# Adafruit_2_13in_eInk_Bonnet.net
KiCad netlist of a schematic drawn in EAGLE
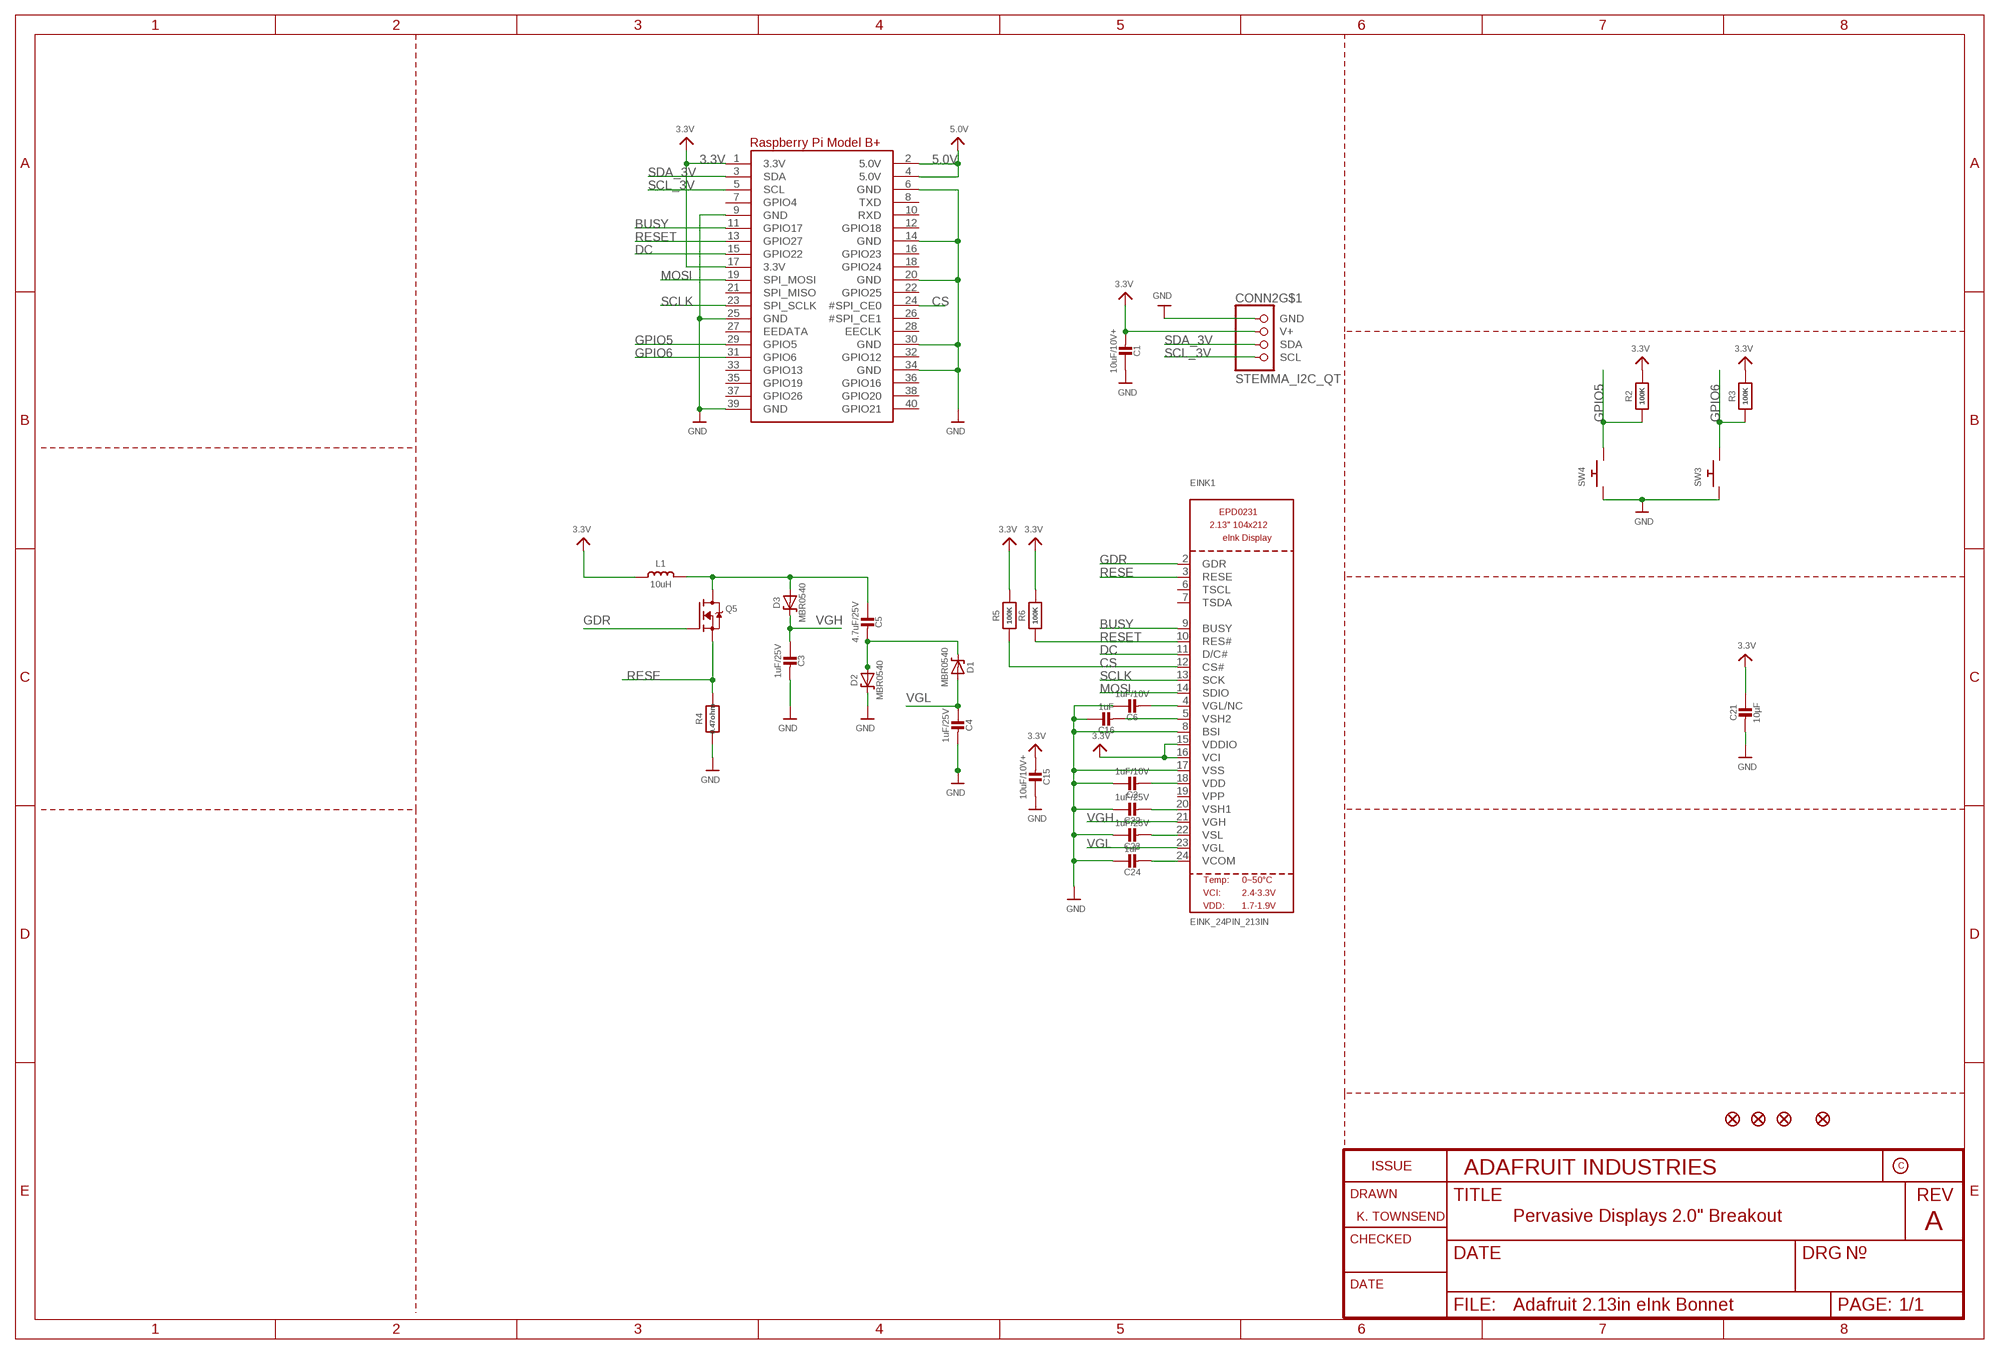
[diagram p0: schematic, sheet 1]

(export (version "E")
  (design (tool "Eeschema 10.0.6"))
  (components
    (comp (ref "C1")
      (value "10uF/10V+")
      (footprint "eagle-import:0805-NO")
      (libsource (lib "eagle-import") (part "CAP_CERAMIC0805-NOOUTLINE"))
    )
    (comp (ref "C2")
      (value "1uF/10V")
      (footprint "eagle-import:0805-NO")
      (libsource (lib "eagle-import") (part "CAP_CERAMIC0805-NOOUTLINE"))
    )
    (comp (ref "C3")
      (value "1uF/25V")
      (footprint "eagle-import:0805-NO")
      (libsource (lib "eagle-import") (part "CAP_CERAMIC0805-NOOUTLINE"))
    )
    (comp (ref "C4")
      (value "1uF/25V")
      (footprint "eagle-import:0805-NO")
      (libsource (lib "eagle-import") (part "CAP_CERAMIC0805-NOOUTLINE"))
    )
    (comp (ref "C5")
      (value "4.7uF/25V")
      (footprint "eagle-import:0805-NO")
      (libsource (lib "eagle-import") (part "CAP_CERAMIC0805-NOOUTLINE"))
    )
    (comp (ref "C6")
      (value "1uF/10V")
      (footprint "eagle-import:0805-NO")
      (libsource (lib "eagle-import") (part "CAP_CERAMIC0805-NOOUTLINE"))
    )
    (comp (ref "C15")
      (value "10uF/10V+")
      (footprint "eagle-import:0805-NO")
      (libsource (lib "eagle-import") (part "CAP_CERAMIC0805-NOOUTLINE"))
    )
    (comp (ref "C16")
      (value "1uF")
      (footprint "eagle-import:0805-NO")
      (libsource (lib "eagle-import") (part "CAP_CERAMIC0805-NOOUTLINE"))
    )
    (comp (ref "C21")
      (value "10µF")
      (footprint "eagle-import:0805-NO")
      (libsource (lib "eagle-import") (part "CAP_CERAMIC0805-NOOUTLINE"))
    )
    (comp (ref "C22")
      (value "1uF/25V")
      (footprint "eagle-import:0805-NO")
      (libsource (lib "eagle-import") (part "CAP_CERAMIC0805-NOOUTLINE"))
    )
    (comp (ref "C23")
      (value "1uF/25V")
      (footprint "eagle-import:0805-NO")
      (libsource (lib "eagle-import") (part "CAP_CERAMIC0805-NOOUTLINE"))
    )
    (comp (ref "C24")
      (value "1uF")
      (footprint "eagle-import:0805-NO")
      (libsource (lib "eagle-import") (part "CAP_CERAMIC0805-NOOUTLINE"))
    )
    (comp (ref "CONN2")
      (value "STEMMA_I2C_QT")
      (footprint "eagle-import:JST_SH4")
      (libsource (lib "eagle-import") (part "STEMMA_I2C_QT"))
    )
    (comp (ref "D1")
      (value "MBR0540")
      (footprint "eagle-import:SOD-123")
      (libsource (lib "eagle-import") (part "DIODE-SCHOTTKYSOD-123"))
    )
    (comp (ref "D2")
      (value "MBR0540")
      (footprint "eagle-import:SOD-123")
      (libsource (lib "eagle-import") (part "DIODE-SCHOTTKYSOD-123"))
    )
    (comp (ref "D3")
      (value "MBR0540")
      (footprint "eagle-import:SOD-123")
      (libsource (lib "eagle-import") (part "DIODE-SCHOTTKYSOD-123"))
    )
    (comp (ref "EINK1")
      (value "EINK_24PIN_213IN")
      (footprint "eagle-import:EINK_213IN_104X212")
      (libsource (lib "eagle-import") (part "EINK_24PIN_213IN"))
    )
    (comp (ref "FID1")
      (value "FIDUCIAL_1MM")
      (footprint "eagle-import:FIDUCIAL_1MM")
      (libsource (lib "eagle-import") (part "FIDUCIAL_1MM"))
    )
    (comp (ref "FID2")
      (value "FIDUCIAL_1MM")
      (footprint "eagle-import:FIDUCIAL_1MM")
      (libsource (lib "eagle-import") (part "FIDUCIAL_1MM"))
    )
    (comp (ref "FID3")
      (value "FIDUCIAL_1MM")
      (footprint "eagle-import:FIDUCIAL_1MM")
      (libsource (lib "eagle-import") (part "FIDUCIAL_1MM"))
    )
    (comp (ref "FID4")
      (value "FIDUCIAL_1MM")
      (footprint "eagle-import:FIDUCIAL_1MM")
      (libsource (lib "eagle-import") (part "FIDUCIAL_1MM"))
    )
    (comp (ref "L1")
      (value "10uH")
      (footprint "eagle-import:INDUCTOR_4X4MM_NR401")
      (libsource (lib "eagle-import") (part "INDUCTORNR401"))
    )
    (comp (ref "Q5")
      (value "IRLML0100")
      (footprint "eagle-import:SOT23-3")
      (libsource (lib "eagle-import") (part "IRLML2060TRPBF"))
    )
    (comp (ref "R2")
      (value "100K")
      (footprint "eagle-import:0603-NO")
      (libsource (lib "eagle-import") (part "RESISTOR_0603_NOOUT"))
    )
    (comp (ref "R3")
      (value "100K")
      (footprint "eagle-import:0603-NO")
      (libsource (lib "eagle-import") (part "RESISTOR_0603_NOOUT"))
    )
    (comp (ref "R4")
      (value "0.47ohm")
      (footprint "eagle-import:0805_10MGAP")
      (libsource (lib "eagle-import") (part "RESISTOR0805_10MGAP"))
    )
    (comp (ref "R5")
      (value "100K")
      (footprint "eagle-import:0603-NO")
      (libsource (lib "eagle-import") (part "RESISTOR_0603_NOOUT"))
    )
    (comp (ref "R6")
      (value "100K")
      (footprint "eagle-import:0603-NO")
      (libsource (lib "eagle-import") (part "RESISTOR_0603_NOOUT"))
    )
    (comp (ref "RPI2")
      (value "RASPBERRYPI_BPLUS_SMT_NODIM")
      (footprint "eagle-import:PI_BONNET_SMT_NODIM")
      (libsource (lib "eagle-import") (part "RASPBERRYPI_BPLUS_SMT_NODIM"))
    )
    (comp (ref "SW3")
      (value "SWITCH_PUSHBUTTON_3.5X6MM")
      (footprint "eagle-import:TACTILE_3X6MM")
      (libsource (lib "eagle-import") (part "SWITCH_PUSHBUTTON_3.5X6MM"))
    )
    (comp (ref "SW4")
      (value "SWITCH_PUSHBUTTON_3.5X6MM")
      (footprint "eagle-import:TACTILE_3X6MM")
      (libsource (lib "eagle-import") (part "SWITCH_PUSHBUTTON_3.5X6MM"))
    )
  )
  (nets
    (net (code "1") (name "/BUSY") (class "Default")
      (node (ref "EINK1") (pin "9") (pinfunction "BUSY_9") (pintype "output"))
      (node (ref "RPI2") (pin "11") (pinfunction "GPIO17_11") (pintype "bidirectional"))
    )
    (net (code "2") (name "/CS") (class "Default")
      (node (ref "EINK1") (pin "12") (pinfunction "CS#_12") (pintype "input"))
      (node (ref "R5") (pin "1") (pinfunction "1_1") (pintype "passive"))
      (node (ref "RPI2") (pin "24") (pinfunction "#SPI_CE0_24") (pintype "bidirectional"))
    )
    (net (code "3") (name "/DC") (class "Default")
      (node (ref "EINK1") (pin "11") (pinfunction "D/C#_11") (pintype "input"))
      (node (ref "RPI2") (pin "15") (pinfunction "GPIO22_15") (pintype "bidirectional"))
    )
    (net (code "4") (name "/GDR") (class "Default")
      (node (ref "EINK1") (pin "2") (pinfunction "GDR_2") (pintype "output"))
      (node (ref "Q5") (pin "1") (pinfunction "G_1") (pintype "bidirectional"))
    )
    (net (code "5") (name "/GPIO5") (class "Default")
      (node (ref "R2") (pin "1") (pinfunction "1_1") (pintype "passive"))
      (node (ref "RPI2") (pin "29") (pinfunction "GPIO5_29") (pintype "bidirectional"))
      (node (ref "SW4") (pin "P$2") (pinfunction "P$2_P$2") (pintype "passive"))
    )
    (net (code "6") (name "/GPIO6") (class "Default")
      (node (ref "R3") (pin "1") (pinfunction "1_1") (pintype "passive"))
      (node (ref "RPI2") (pin "31") (pinfunction "GPIO6_31") (pintype "bidirectional"))
      (node (ref "SW3") (pin "P$2") (pinfunction "P$2_P$2") (pintype "passive"))
    )
    (net (code "7") (name "/MOSI") (class "Default")
      (node (ref "EINK1") (pin "14") (pinfunction "SDIO_14") (pintype "bidirectional"))
      (node (ref "RPI2") (pin "19") (pinfunction "SPI_MOSI_19") (pintype "bidirectional"))
    )
    (net (code "8") (name "/RESE") (class "Default")
      (node (ref "EINK1") (pin "3") (pinfunction "RESE_3") (pintype "input"))
      (node (ref "Q5") (pin "2") (pinfunction "S_2") (pintype "bidirectional"))
      (node (ref "R4") (pin "1") (pinfunction "1_1") (pintype "passive"))
    )
    (net (code "9") (name "/RESET") (class "Default")
      (node (ref "EINK1") (pin "10") (pinfunction "RES#_10") (pintype "input"))
      (node (ref "R6") (pin "1") (pinfunction "1_1") (pintype "passive"))
      (node (ref "RPI2") (pin "13") (pinfunction "GPIO27_13") (pintype "bidirectional"))
    )
    (net (code "10") (name "/SCLK") (class "Default")
      (node (ref "EINK1") (pin "13") (pinfunction "SCK_13") (pintype "bidirectional"))
      (node (ref "RPI2") (pin "23") (pinfunction "SPI_SCLK_23") (pintype "bidirectional"))
    )
    (net (code "11") (name "/SCL_3V") (class "Default")
      (node (ref "CONN2") (pin "4") (pinfunction "SCL_4") (pintype "passive"))
      (node (ref "RPI2") (pin "5") (pinfunction "SCL_5") (pintype "bidirectional"))
    )
    (net (code "12") (name "/SDA_3V") (class "Default")
      (node (ref "CONN2") (pin "3") (pinfunction "SDA_3") (pintype "passive"))
      (node (ref "RPI2") (pin "3") (pinfunction "SDA_3") (pintype "bidirectional"))
    )
    (net (code "13") (name "/VGH") (class "Default")
      (node (ref "C3") (pin "1") (pinfunction "1_1") (pintype "passive"))
      (node (ref "D3") (pin "C") (pinfunction "C_C") (pintype "passive"))
      (node (ref "EINK1") (pin "21") (pinfunction "VGH_21") (pintype "passive"))
    )
    (net (code "14") (name "/VGL") (class "Default")
      (node (ref "C4") (pin "1") (pinfunction "1_1") (pintype "passive"))
      (node (ref "D1") (pin "A") (pinfunction "A_A") (pintype "passive"))
      (node (ref "EINK1") (pin "23") (pinfunction "VGL_23") (pintype "passive"))
    )
    (net (code "15") (name "3.3V") (class "Default")
      (node (ref "C1") (pin "2") (pinfunction "2_2") (pintype "passive"))
      (node (ref "C15") (pin "2") (pinfunction "2_2") (pintype "passive"))
      (node (ref "C21") (pin "1") (pinfunction "1_1") (pintype "passive"))
      (node (ref "CONN2") (pin "2") (pinfunction "V+_2") (pintype "passive"))
      (node (ref "EINK1") (pin "15") (pinfunction "VDDIO_15") (pintype "power_in"))
      (node (ref "EINK1") (pin "16") (pinfunction "VCI_16") (pintype "power_in"))
      (node (ref "L1") (pin "P$2") (pinfunction "2_P$2") (pintype "passive"))
      (node (ref "R2") (pin "2") (pinfunction "2_2") (pintype "passive"))
      (node (ref "R3") (pin "2") (pinfunction "2_2") (pintype "passive"))
      (node (ref "R5") (pin "2") (pinfunction "2_2") (pintype "passive"))
      (node (ref "R6") (pin "2") (pinfunction "2_2") (pintype "passive"))
      (node (ref "RPI2") (pin "1") (pinfunction "3.3V_1") (pintype "power_in"))
      (node (ref "RPI2") (pin "17") (pinfunction "3.3V_17") (pintype "power_in"))
    )
    (net (code "16") (name "5.0V") (class "Default")
      (node (ref "RPI2") (pin "2") (pinfunction "5.0V_2") (pintype "power_in"))
      (node (ref "RPI2") (pin "4") (pinfunction "5.0V_4") (pintype "power_in"))
    )
    (net (code "17") (name "GND") (class "Default")
      (node (ref "C1") (pin "1") (pinfunction "1_1") (pintype "passive"))
      (node (ref "C15") (pin "1") (pinfunction "1_1") (pintype "passive"))
      (node (ref "C16") (pin "1") (pinfunction "1_1") (pintype "passive"))
      (node (ref "C2") (pin "1") (pinfunction "1_1") (pintype "passive"))
      (node (ref "C21") (pin "2") (pinfunction "2_2") (pintype "passive"))
      (node (ref "C22") (pin "1") (pinfunction "1_1") (pintype "passive"))
      (node (ref "C23") (pin "1") (pinfunction "1_1") (pintype "passive"))
      (node (ref "C24") (pin "1") (pinfunction "1_1") (pintype "passive"))
      (node (ref "C3") (pin "2") (pinfunction "2_2") (pintype "passive"))
      (node (ref "C4") (pin "2") (pinfunction "2_2") (pintype "passive"))
      (node (ref "C6") (pin "1") (pinfunction "1_1") (pintype "passive"))
      (node (ref "CONN2") (pin "1") (pinfunction "GND_1") (pintype "passive"))
      (node (ref "D2") (pin "C") (pinfunction "C_C") (pintype "passive"))
      (node (ref "EINK1") (pin "17") (pinfunction "VSS_17") (pintype "power_in"))
      (node (ref "EINK1") (pin "8") (pinfunction "BSI_8") (pintype "input"))
      (node (ref "R4") (pin "2") (pinfunction "2_2") (pintype "passive"))
      (node (ref "RPI2") (pin "14") (pinfunction "GND_14") (pintype "power_in"))
      (node (ref "RPI2") (pin "20") (pinfunction "GND_20") (pintype "power_in"))
      (node (ref "RPI2") (pin "25") (pinfunction "GND_25") (pintype "power_in"))
      (node (ref "RPI2") (pin "30") (pinfunction "GND_30") (pintype "power_in"))
      (node (ref "RPI2") (pin "34") (pinfunction "GND_34") (pintype "power_in"))
      (node (ref "RPI2") (pin "39") (pinfunction "GND_39") (pintype "power_in"))
      (node (ref "RPI2") (pin "6") (pinfunction "GND_6") (pintype "power_in"))
      (node (ref "RPI2") (pin "9") (pinfunction "GND_9") (pintype "power_in"))
      (node (ref "SW3") (pin "P$1") (pinfunction "P$1_P$1") (pintype "passive"))
      (node (ref "SW4") (pin "P$1") (pinfunction "P$1_P$1") (pintype "passive"))
    )
    (net (code "18") (name "Net-(C5-Pad2)") (class "Default")
      (node (ref "C5") (pin "2") (pinfunction "2_2") (pintype "passive"))
      (node (ref "D1") (pin "C") (pinfunction "C_C") (pintype "passive"))
      (node (ref "D2") (pin "A") (pinfunction "A_A") (pintype "passive"))
    )
    (net (code "19") (name "Net-(EINK1-VCOM)") (class "Default")
      (node (ref "C24") (pin "2") (pinfunction "2_2") (pintype "passive"))
      (node (ref "EINK1") (pin "24") (pinfunction "VCOM_24") (pintype "passive"))
    )
    (net (code "20") (name "Net-(EINK1-VDD)") (class "Default")
      (node (ref "C2") (pin "2") (pinfunction "2_2") (pintype "passive"))
      (node (ref "EINK1") (pin "18") (pinfunction "VDD_18") (pintype "passive"))
    )
    (net (code "21") (name "Net-(EINK1-VGL{slash}NC)") (class "Default")
      (node (ref "C6") (pin "2") (pinfunction "2_2") (pintype "passive"))
      (node (ref "EINK1") (pin "4") (pinfunction "VGL/NC_4") (pintype "bidirectional"))
    )
    (net (code "22") (name "Net-(EINK1-VSH1)") (class "Default")
      (node (ref "C22") (pin "2") (pinfunction "2_2") (pintype "passive"))
      (node (ref "EINK1") (pin "20") (pinfunction "VSH1_20") (pintype "passive"))
    )
    (net (code "23") (name "Net-(EINK1-VSH2)") (class "Default")
      (node (ref "C16") (pin "2") (pinfunction "2_2") (pintype "passive"))
      (node (ref "EINK1") (pin "5") (pinfunction "VSH2_5") (pintype "passive"))
    )
    (net (code "24") (name "Net-(EINK1-VSL)") (class "Default")
      (node (ref "C23") (pin "2") (pinfunction "2_2") (pintype "passive"))
      (node (ref "EINK1") (pin "22") (pinfunction "VSL_22") (pintype "passive"))
    )
    (net (code "25") (name "Net-(L1-1)") (class "Default")
      (node (ref "C5") (pin "1") (pinfunction "1_1") (pintype "passive"))
      (node (ref "D3") (pin "A") (pinfunction "A_A") (pintype "passive"))
      (node (ref "L1") (pin "P$1") (pinfunction "1_P$1") (pintype "passive"))
      (node (ref "Q5") (pin "3") (pinfunction "D_3") (pintype "bidirectional"))
    )
    (net (code "26") (name "unconnected-(EINK1-TSCL-Pad6)") (class "Default")
      (node (ref "EINK1") (pin "6") (pinfunction "TSCL_6") (pintype "output"))
    )
    (net (code "27") (name "unconnected-(EINK1-TSDA-Pad7)") (class "Default")
      (node (ref "EINK1") (pin "7") (pinfunction "TSDA_7") (pintype "bidirectional"))
    )
    (net (code "28") (name "unconnected-(EINK1-VPP-Pad19)") (class "Default")
      (node (ref "EINK1") (pin "19") (pinfunction "VPP_19") (pintype "passive"))
    )
    (net (code "29") (name "unconnected-(RPI2-#SPI_CE1-Pad26)") (class "Default")
      (node (ref "RPI2") (pin "26") (pinfunction "#SPI_CE1_26") (pintype "bidirectional"))
    )
    (net (code "30") (name "unconnected-(RPI2-EECLK-Pad28)") (class "Default")
      (node (ref "RPI2") (pin "28") (pinfunction "EECLK_28") (pintype "bidirectional"))
    )
    (net (code "31") (name "unconnected-(RPI2-EEDATA-Pad27)") (class "Default")
      (node (ref "RPI2") (pin "27") (pinfunction "EEDATA_27") (pintype "bidirectional"))
    )
    (net (code "32") (name "unconnected-(RPI2-GPIO4-Pad7)") (class "Default")
      (node (ref "RPI2") (pin "7") (pinfunction "GPIO4_7") (pintype "bidirectional"))
    )
    (net (code "33") (name "unconnected-(RPI2-GPIO12-Pad32)") (class "Default")
      (node (ref "RPI2") (pin "32") (pinfunction "GPIO12_32") (pintype "bidirectional"))
    )
    (net (code "34") (name "unconnected-(RPI2-GPIO13-Pad33)") (class "Default")
      (node (ref "RPI2") (pin "33") (pinfunction "GPIO13_33") (pintype "bidirectional"))
    )
    (net (code "35") (name "unconnected-(RPI2-GPIO16-Pad36)") (class "Default")
      (node (ref "RPI2") (pin "36") (pinfunction "GPIO16_36") (pintype "bidirectional"))
    )
    (net (code "36") (name "unconnected-(RPI2-GPIO18-Pad12)") (class "Default")
      (node (ref "RPI2") (pin "12") (pinfunction "GPIO18_12") (pintype "bidirectional"))
    )
    (net (code "37") (name "unconnected-(RPI2-GPIO19-Pad35)") (class "Default")
      (node (ref "RPI2") (pin "35") (pinfunction "GPIO19_35") (pintype "bidirectional"))
    )
    (net (code "38") (name "unconnected-(RPI2-GPIO20-Pad38)") (class "Default")
      (node (ref "RPI2") (pin "38") (pinfunction "GPIO20_38") (pintype "bidirectional"))
    )
    (net (code "39") (name "unconnected-(RPI2-GPIO21-Pad40)") (class "Default")
      (node (ref "RPI2") (pin "40") (pinfunction "GPIO21_40") (pintype "bidirectional"))
    )
    (net (code "40") (name "unconnected-(RPI2-GPIO23-Pad16)") (class "Default")
      (node (ref "RPI2") (pin "16") (pinfunction "GPIO23_16") (pintype "bidirectional"))
    )
    (net (code "41") (name "unconnected-(RPI2-GPIO24-Pad18)") (class "Default")
      (node (ref "RPI2") (pin "18") (pinfunction "GPIO24_18") (pintype "bidirectional"))
    )
    (net (code "42") (name "unconnected-(RPI2-GPIO25-Pad22)") (class "Default")
      (node (ref "RPI2") (pin "22") (pinfunction "GPIO25_22") (pintype "bidirectional"))
    )
    (net (code "43") (name "unconnected-(RPI2-GPIO26-Pad37)") (class "Default")
      (node (ref "RPI2") (pin "37") (pinfunction "GPIO26_37") (pintype "bidirectional"))
    )
    (net (code "44") (name "unconnected-(RPI2-RXD-Pad10)") (class "Default")
      (node (ref "RPI2") (pin "10") (pinfunction "RXD_10") (pintype "bidirectional"))
    )
    (net (code "45") (name "unconnected-(RPI2-SPI_MISO-Pad21)") (class "Default")
      (node (ref "RPI2") (pin "21") (pinfunction "SPI_MISO_21") (pintype "bidirectional"))
    )
    (net (code "46") (name "unconnected-(RPI2-TXD-Pad8)") (class "Default")
      (node (ref "RPI2") (pin "8") (pinfunction "TXD_8") (pintype "bidirectional"))
    )
  )
)
